# main.net
KiCad netlist of a schematic drawn in EAGLE
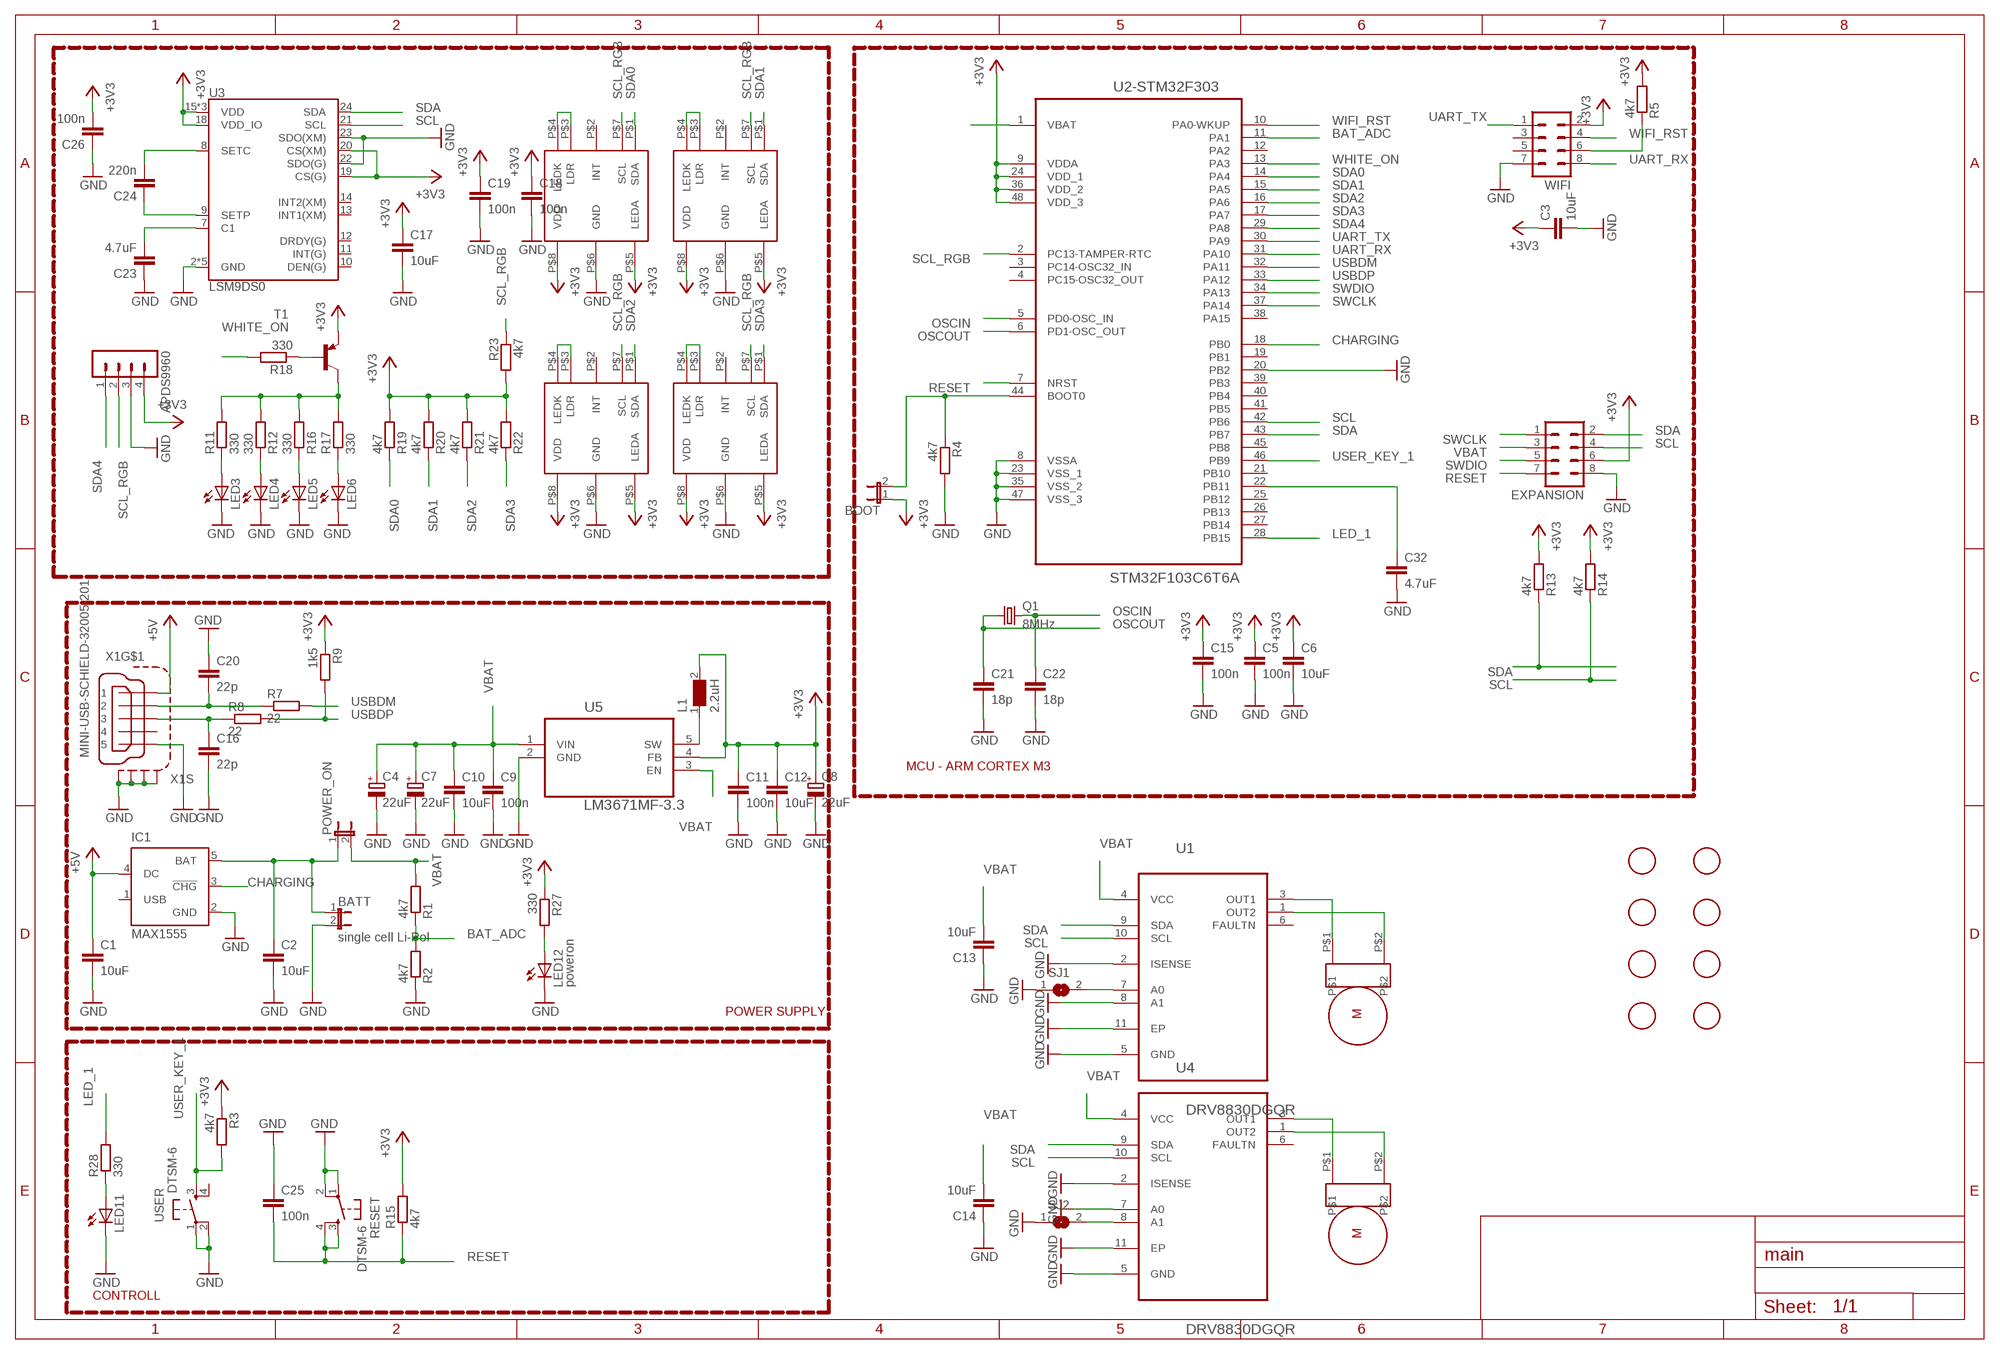
[diagram p0: schematic, sheet 1]

(export (version "E")
  (design (tool "Eeschema 10.0.6"))
  (components
    (comp (ref "APDS9960")
      (value "MA04-1")
      (footprint "eagle-import:MA04-1")
      (libsource (lib "eagle-import") (part "MA04-1"))
    )
    (comp (ref "BATT")
      (value "single cell Li-Pol")
      (footprint "eagle-import:JP1")
      (libsource (lib "eagle-import") (part "JP1E"))
    )
    (comp (ref "BOOT")
      (value "JP1E")
      (footprint "eagle-import:JP1")
      (libsource (lib "eagle-import") (part "JP1E"))
    )
    (comp (ref "C1")
      (value "10uF")
      (footprint "eagle-import:C0805")
      (libsource (lib "eagle-import") (part "C-EUC0805"))
    )
    (comp (ref "C2")
      (value "10uF")
      (footprint "eagle-import:C0805")
      (libsource (lib "eagle-import") (part "C-EUC0805"))
    )
    (comp (ref "C3")
      (value "10uF")
      (footprint "eagle-import:C0805")
      (libsource (lib "eagle-import") (part "C-EUC0805"))
    )
    (comp (ref "C4")
      (value "22uF")
      (footprint "eagle-import:153CLV-0505")
      (libsource (lib "eagle-import") (part "CPOL-EU153CLV-0505"))
    )
    (comp (ref "C5")
      (value "100n")
      (footprint "eagle-import:C0805")
      (libsource (lib "eagle-import") (part "C-EUC0805"))
    )
    (comp (ref "C6")
      (value "10uF")
      (footprint "eagle-import:C0805")
      (libsource (lib "eagle-import") (part "C-EUC0805"))
    )
    (comp (ref "C7")
      (value "22uF")
      (footprint "eagle-import:153CLV-0505")
      (libsource (lib "eagle-import") (part "CPOL-EU153CLV-0505"))
    )
    (comp (ref "C8")
      (value "22uF")
      (footprint "eagle-import:153CLV-0505")
      (libsource (lib "eagle-import") (part "CPOL-EU153CLV-0505"))
    )
    (comp (ref "C9")
      (value "100n")
      (footprint "eagle-import:C0805")
      (libsource (lib "eagle-import") (part "C-EUC0805"))
    )
    (comp (ref "C10")
      (value "10uF")
      (footprint "eagle-import:C0805")
      (libsource (lib "eagle-import") (part "C-EUC0805"))
    )
    (comp (ref "C11")
      (value "100n")
      (footprint "eagle-import:C0805")
      (libsource (lib "eagle-import") (part "C-EUC0805"))
    )
    (comp (ref "C12")
      (value "10uF")
      (footprint "eagle-import:C0805")
      (libsource (lib "eagle-import") (part "C-EUC0805"))
    )
    (comp (ref "C13")
      (value "10uF")
      (footprint "eagle-import:C0805")
      (libsource (lib "eagle-import") (part "C-EUC0805"))
    )
    (comp (ref "C14")
      (value "10uF")
      (footprint "eagle-import:C0805")
      (libsource (lib "eagle-import") (part "C-EUC0805"))
    )
    (comp (ref "C15")
      (value "100n")
      (footprint "eagle-import:C0805")
      (libsource (lib "eagle-import") (part "C-EUC0805"))
    )
    (comp (ref "C16")
      (value "22p")
      (footprint "eagle-import:C0805")
      (libsource (lib "eagle-import") (part "C-EUC0805"))
    )
    (comp (ref "C17")
      (value "10uF")
      (footprint "eagle-import:C0805")
      (libsource (lib "eagle-import") (part "C-EUC0805"))
    )
    (comp (ref "C18")
      (value "100n")
      (footprint "eagle-import:C0805")
      (libsource (lib "eagle-import") (part "C-EUC0805"))
    )
    (comp (ref "C19")
      (value "100n")
      (footprint "eagle-import:C0805")
      (libsource (lib "eagle-import") (part "C-EUC0805"))
    )
    (comp (ref "C20")
      (value "22p")
      (footprint "eagle-import:C0805")
      (libsource (lib "eagle-import") (part "C-EUC0805"))
    )
    (comp (ref "C21")
      (value "18p")
      (footprint "eagle-import:C0805")
      (libsource (lib "eagle-import") (part "C-EUC0805"))
    )
    (comp (ref "C22")
      (value "18p")
      (footprint "eagle-import:C0805")
      (libsource (lib "eagle-import") (part "C-EUC0805"))
    )
    (comp (ref "C23")
      (value "4.7uF")
      (footprint "eagle-import:C0805")
      (libsource (lib "eagle-import") (part "C-EUC0805"))
    )
    (comp (ref "C24")
      (value "220n")
      (footprint "eagle-import:C0805")
      (libsource (lib "eagle-import") (part "C-EUC0805"))
    )
    (comp (ref "C25")
      (value "100n")
      (footprint "eagle-import:C0805")
      (libsource (lib "eagle-import") (part "C-EUC0805"))
    )
    (comp (ref "C26")
      (value "100n")
      (footprint "eagle-import:C0805")
      (libsource (lib "eagle-import") (part "C-EUC0805"))
    )
    (comp (ref "C32")
      (value "4.7uF")
      (footprint "eagle-import:C0805")
      (libsource (lib "eagle-import") (part "C-EUC0805"))
    )
    (comp (ref "EXPANSION")
      (value "MA04-2")
      (footprint "eagle-import:MA04-2")
      (libsource (lib "eagle-import") (part "MA04-2"))
    )
    (comp (ref "IC1")
      (value "MAX1555")
      (footprint "eagle-import:SOT23-5L")
      (fields (field (name "MF") "MAXIM") (field (name "MPN") "MAX1555EZK+T"))
      (libsource (lib "eagle-import") (part "MAX1555"))
    )
    (comp (ref "L1")
      (value "2.2uH")
      (footprint "eagle-import:WE-LQ_M")
      (fields (field (name "MPN") "744032002 "))
      (libsource (lib "eagle-import") (part "WE-LQ_M-744032002"))
    )
    (comp (ref "LED3")
      (value "LEDCHIPLED_1206")
      (footprint "eagle-import:CHIPLED_1206")
      (libsource (lib "eagle-import") (part "LEDCHIPLED_1206"))
    )
    (comp (ref "LED4")
      (value "LEDCHIPLED_1206")
      (footprint "eagle-import:CHIPLED_1206")
      (libsource (lib "eagle-import") (part "LEDCHIPLED_1206"))
    )
    (comp (ref "LED5")
      (value "LEDCHIPLED_1206")
      (footprint "eagle-import:CHIPLED_1206")
      (libsource (lib "eagle-import") (part "LEDCHIPLED_1206"))
    )
    (comp (ref "LED6")
      (value "LEDCHIPLED_1206")
      (footprint "eagle-import:CHIPLED_1206")
      (libsource (lib "eagle-import") (part "LEDCHIPLED_1206"))
    )
    (comp (ref "LED11")
      (value "LEDCHIPLED_1206")
      (footprint "eagle-import:CHIPLED_1206")
      (libsource (lib "eagle-import") (part "LEDCHIPLED_1206"))
    )
    (comp (ref "LED12")
      (value "poweron")
      (footprint "eagle-import:CHIPLED_1206")
      (libsource (lib "eagle-import") (part "LEDCHIPLED_1206"))
    )
    (comp (ref "POWER_ON")
      (value "JP1E")
      (footprint "eagle-import:JP1")
      (libsource (lib "eagle-import") (part "JP1E"))
    )
    (comp (ref "Q1")
      (value "8MHz")
      (footprint "eagle-import:CTS406")
      (libsource (lib "eagle-import") (part "CRYSTALCTS406"))
    )
    (comp (ref "R1")
      (value "4k7")
      (footprint "eagle-import:M0805")
      (libsource (lib "eagle-import") (part "R-EU_M0805"))
    )
    (comp (ref "R2")
      (value "4k7")
      (footprint "eagle-import:M0805")
      (libsource (lib "eagle-import") (part "R-EU_M0805"))
    )
    (comp (ref "R3")
      (value "4k7")
      (footprint "eagle-import:M1206")
      (libsource (lib "eagle-import") (part "R-EU_M1206"))
    )
    (comp (ref "R4")
      (value "4k7")
      (footprint "eagle-import:M0805")
      (libsource (lib "eagle-import") (part "R-EU_M0805"))
    )
    (comp (ref "R5")
      (value "4k7")
      (footprint "eagle-import:M0805")
      (libsource (lib "eagle-import") (part "R-EU_M0805"))
    )
    (comp (ref "R7")
      (value "22")
      (footprint "eagle-import:M0805")
      (libsource (lib "eagle-import") (part "R-EU_M0805"))
    )
    (comp (ref "R8")
      (value "22")
      (footprint "eagle-import:M0805")
      (libsource (lib "eagle-import") (part "R-EU_M0805"))
    )
    (comp (ref "R9")
      (value "1k5")
      (footprint "eagle-import:M0805")
      (libsource (lib "eagle-import") (part "R-EU_M0805"))
    )
    (comp (ref "R11")
      (value "330")
      (footprint "eagle-import:M0805")
      (libsource (lib "eagle-import") (part "R-EU_M0805"))
    )
    (comp (ref "R12")
      (value "330")
      (footprint "eagle-import:M0805")
      (libsource (lib "eagle-import") (part "R-EU_M0805"))
    )
    (comp (ref "R13")
      (value "4k7")
      (footprint "eagle-import:M0805")
      (libsource (lib "eagle-import") (part "R-EU_M0805"))
    )
    (comp (ref "R14")
      (value "4k7")
      (footprint "eagle-import:M0805")
      (libsource (lib "eagle-import") (part "R-EU_M0805"))
    )
    (comp (ref "R15")
      (value "4k7")
      (footprint "eagle-import:M0805")
      (libsource (lib "eagle-import") (part "R-EU_M0805"))
    )
    (comp (ref "R16")
      (value "330")
      (footprint "eagle-import:M0805")
      (libsource (lib "eagle-import") (part "R-EU_M0805"))
    )
    (comp (ref "R17")
      (value "330")
      (footprint "eagle-import:M0805")
      (libsource (lib "eagle-import") (part "R-EU_M0805"))
    )
    (comp (ref "R18")
      (value "330")
      (footprint "eagle-import:M0805")
      (libsource (lib "eagle-import") (part "R-EU_M0805"))
    )
    (comp (ref "R19")
      (value "4k7")
      (footprint "eagle-import:M0805")
      (libsource (lib "eagle-import") (part "R-EU_M0805"))
    )
    (comp (ref "R20")
      (value "4k7")
      (footprint "eagle-import:M0805")
      (libsource (lib "eagle-import") (part "R-EU_M0805"))
    )
    (comp (ref "R21")
      (value "4k7")
      (footprint "eagle-import:M0805")
      (libsource (lib "eagle-import") (part "R-EU_M0805"))
    )
    (comp (ref "R22")
      (value "4k7")
      (footprint "eagle-import:M0805")
      (libsource (lib "eagle-import") (part "R-EU_M0805"))
    )
    (comp (ref "R23")
      (value "4k7")
      (footprint "eagle-import:M0805")
      (libsource (lib "eagle-import") (part "R-EU_M0805"))
    )
    (comp (ref "R27")
      (value "330")
      (footprint "eagle-import:M0805")
      (libsource (lib "eagle-import") (part "R-EU_M0805"))
    )
    (comp (ref "R28")
      (value "330")
      (footprint "eagle-import:M0805")
      (libsource (lib "eagle-import") (part "R-EU_M0805"))
    )
    (comp (ref "RESET")
      (value "DTSM-6")
      (footprint "eagle-import:DTSM-6")
      (libsource (lib "eagle-import") (part "DTSM-6"))
    )
    (comp (ref "SJ1") (value "SJ") (footprint "eagle-import:SJ") (libsource (lib "eagle-import") (part "SJ")))
    (comp (ref "SJ2") (value "SJ") (footprint "eagle-import:SJ") (libsource (lib "eagle-import") (part "SJ")))
    (comp (ref "T1")
      (value "BC857A-PNP-SOT23-BEC")
      (footprint "eagle-import:SOT23-BEC")
      (libsource (lib "eagle-import") (part "-PNP-SOT23-BECBC857A"))
    )
    (comp (ref "U$1")
      (value "APDS9950")
      (footprint "eagle-import:APDS9950")
      (libsource (lib "eagle-import") (part "APDS9950"))
    )
    (comp (ref "U$2")
      (value "APDS9950")
      (footprint "eagle-import:APDS9950")
      (libsource (lib "eagle-import") (part "APDS9950"))
    )
    (comp (ref "U$3")
      (value "APDS9950")
      (footprint "eagle-import:APDS9950")
      (libsource (lib "eagle-import") (part "APDS9950"))
    )
    (comp (ref "U$4")
      (value "APDS9950")
      (footprint "eagle-import:APDS9950")
      (libsource (lib "eagle-import") (part "APDS9950"))
    )
    (comp (ref "U$5")
      (value "MICRO_METAL_GEAR_MOTOR")
      (footprint "eagle-import:MICRO_METAL_GEAR_MOTOR")
      (libsource (lib "eagle-import") (part "MICRO_METAL_GEAR_MOTOR"))
    )
    (comp (ref "U$6")
      (value "MICRO_METAL_GEAR_MOTOR")
      (footprint "eagle-import:MICRO_METAL_GEAR_MOTOR")
      (libsource (lib "eagle-import") (part "MICRO_METAL_GEAR_MOTOR"))
    )
    (comp (ref "U$9")
      (value "FIDUCIAL")
      (footprint "eagle-import:FIDUCIAL_1MM")
      (libsource (lib "eagle-import") (part "FIDUCIAL"))
    )
    (comp (ref "U$10")
      (value "FIDUCIAL")
      (footprint "eagle-import:FIDUCIAL_1MM")
      (libsource (lib "eagle-import") (part "FIDUCIAL"))
    )
    (comp (ref "U$11")
      (value "FIDUCIAL")
      (footprint "eagle-import:FIDUCIAL_1MM")
      (libsource (lib "eagle-import") (part "FIDUCIAL"))
    )
    (comp (ref "U$12")
      (value "FIDUCIAL")
      (footprint "eagle-import:FIDUCIAL_1MM")
      (libsource (lib "eagle-import") (part "FIDUCIAL"))
    )
    (comp (ref "U$13")
      (value "FIDUCIAL")
      (footprint "eagle-import:FIDUCIAL_1MM")
      (libsource (lib "eagle-import") (part "FIDUCIAL"))
    )
    (comp (ref "U$14")
      (value "FIDUCIAL")
      (footprint "eagle-import:FIDUCIAL_1MM")
      (libsource (lib "eagle-import") (part "FIDUCIAL"))
    )
    (comp (ref "U$15")
      (value "FIDUCIAL")
      (footprint "eagle-import:FIDUCIAL_1MM")
      (libsource (lib "eagle-import") (part "FIDUCIAL"))
    )
    (comp (ref "U$16")
      (value "FIDUCIAL")
      (footprint "eagle-import:FIDUCIAL_1MM")
      (libsource (lib "eagle-import") (part "FIDUCIAL"))
    )
    (comp (ref "U1")
      (value "DRV8830DGQR")
      (footprint "eagle-import:SOP65P640X110-15N")
      (libsource (lib "eagle-import") (part "DRV8830DGQR"))
    )
    (comp (ref "U2-STM32F303")
      (value "STM32F103C6T6A")
      (footprint "eagle-import:QFP50P900X900X160-48N")
      (libsource (lib "eagle-import") (part "STM32F103C6T6A"))
    )
    (comp (ref "U3")
      (value "LSM9DS0")
      (footprint "eagle-import:LGA-24")
      (libsource (lib "eagle-import") (part "LSM9DS0"))
    )
    (comp (ref "U4")
      (value "DRV8830DGQR")
      (footprint "eagle-import:SOP65P640X110-15N")
      (libsource (lib "eagle-import") (part "DRV8830DGQR"))
    )
    (comp (ref "U5")
      (value "LM3671MF-3.3")
      (footprint "eagle-import:SOT95P284X122-5N")
      (libsource (lib "eagle-import") (part "LM3671MF-3.3"))
    )
    (comp (ref "USER")
      (value "DTSM-6")
      (footprint "eagle-import:DTSM-6")
      (libsource (lib "eagle-import") (part "DTSM-6"))
    )
    (comp (ref "WIFI")
      (value "MA04-2")
      (footprint "eagle-import:MA04-2")
      (libsource (lib "eagle-import") (part "MA04-2"))
    )
    (comp (ref "X1")
      (value "MINI-USB-SCHIELD-32005-201")
      (footprint "eagle-import:32005-201")
      (libsource (lib "eagle-import") (part "MINI-USB-SCHIELD-32005-201"))
    )
  )
  (nets
    (net (code "1") (name "+3V3") (class "Default")
      (node (ref "APDS9960") (pin "4") (pinfunction "4_4") (pintype "passive"))
      (node (ref "BOOT") (pin "1") (pinfunction "1_1") (pintype "passive"))
      (node (ref "C11") (pin "1") (pinfunction "1_1") (pintype "passive"))
      (node (ref "C12") (pin "1") (pinfunction "1_1") (pintype "passive"))
      (node (ref "C15") (pin "1") (pinfunction "1_1") (pintype "passive"))
      (node (ref "C17") (pin "1") (pinfunction "1_1") (pintype "passive"))
      (node (ref "C18") (pin "1") (pinfunction "1_1") (pintype "passive"))
      (node (ref "C19") (pin "1") (pinfunction "1_1") (pintype "passive"))
      (node (ref "C26") (pin "2") (pinfunction "2_2") (pintype "passive"))
      (node (ref "C3") (pin "1") (pinfunction "1_1") (pintype "passive"))
      (node (ref "C5") (pin "1") (pinfunction "1_1") (pintype "passive"))
      (node (ref "C6") (pin "1") (pinfunction "1_1") (pintype "passive"))
      (node (ref "C8") (pin "+") (pinfunction "+_+") (pintype "passive"))
      (node (ref "EXPANSION") (pin "6") (pinfunction "6_6") (pintype "passive"))
      (node (ref "L1") (pin "2") (pinfunction "2_2") (pintype "passive"))
      (node (ref "R13") (pin "2") (pinfunction "2_2") (pintype "passive"))
      (node (ref "R14") (pin "2") (pinfunction "2_2") (pintype "passive"))
      (node (ref "R15") (pin "2") (pinfunction "2_2") (pintype "passive"))
      (node (ref "R19") (pin "2") (pinfunction "2_2") (pintype "passive"))
      (node (ref "R20") (pin "2") (pinfunction "2_2") (pintype "passive"))
      (node (ref "R21") (pin "2") (pinfunction "2_2") (pintype "passive"))
      (node (ref "R22") (pin "2") (pinfunction "2_2") (pintype "passive"))
      (node (ref "R23") (pin "2") (pinfunction "2_2") (pintype "passive"))
      (node (ref "R27") (pin "1") (pinfunction "1_1") (pintype "passive"))
      (node (ref "R3") (pin "1") (pinfunction "1_1") (pintype "passive"))
      (node (ref "R5") (pin "2") (pinfunction "2_2") (pintype "passive"))
      (node (ref "R9") (pin "1") (pinfunction "1_1") (pintype "passive"))
      (node (ref "T1") (pin "E") (pinfunction "E_E") (pintype "passive"))
      (node (ref "U$1") (pin "P$5") (pinfunction "LEDA_P$5") (pintype "bidirectional"))
      (node (ref "U$1") (pin "P$8") (pinfunction "VDD_P$8") (pintype "bidirectional"))
      (node (ref "U$2") (pin "P$5") (pinfunction "LEDA_P$5") (pintype "bidirectional"))
      (node (ref "U$2") (pin "P$8") (pinfunction "VDD_P$8") (pintype "bidirectional"))
      (node (ref "U$3") (pin "P$5") (pinfunction "LEDA_P$5") (pintype "bidirectional"))
      (node (ref "U$3") (pin "P$8") (pinfunction "VDD_P$8") (pintype "bidirectional"))
      (node (ref "U$4") (pin "P$5") (pinfunction "LEDA_P$5") (pintype "bidirectional"))
      (node (ref "U$4") (pin "P$8") (pinfunction "VDD_P$8") (pintype "bidirectional"))
      (node (ref "U2-STM32F303") (pin "24") (pinfunction "VDD_1_24") (pintype "power_in"))
      (node (ref "U2-STM32F303") (pin "36") (pinfunction "VDD_2_36") (pintype "power_in"))
      (node (ref "U2-STM32F303") (pin "48") (pinfunction "VDD_3_48") (pintype "power_in"))
      (node (ref "U2-STM32F303") (pin "9") (pinfunction "VDDA_9") (pintype "power_in"))
      (node (ref "U3") (pin "15") (pinfunction "VDD_15") (pintype "bidirectional"))
      (node (ref "U3") (pin "16") (pinfunction "VDD_16") (pintype "bidirectional"))
      (node (ref "U3") (pin "17") (pinfunction "VDD_17") (pintype "bidirectional"))
      (node (ref "U3") (pin "18") (pinfunction "VDD_IO_18") (pintype "bidirectional"))
      (node (ref "U3") (pin "19") (pinfunction "CS(G)_19") (pintype "bidirectional"))
      (node (ref "U3") (pin "20") (pinfunction "CS(XM)_20") (pintype "bidirectional"))
      (node (ref "U5") (pin "4") (pinfunction "FB_4") (pintype "passive"))
      (node (ref "WIFI") (pin "2") (pinfunction "2_2") (pintype "passive"))
    )
    (net (code "2") (name "+5V") (class "Default")
      (node (ref "C1") (pin "1") (pinfunction "1_1") (pintype "passive"))
      (node (ref "IC1") (pin "4") (pinfunction "DC_4") (pintype "input"))
      (node (ref "X1") (pin "1") (pinfunction "1_1") (pintype "passive"))
    )
    (net (code "3") (name "/BAT_ADC") (class "Default")
      (node (ref "R1") (pin "1") (pinfunction "1_1") (pintype "passive"))
      (node (ref "R2") (pin "2") (pinfunction "2_2") (pintype "passive"))
      (node (ref "U2-STM32F303") (pin "11") (pinfunction "PA1_11") (pintype "bidirectional"))
    )
    (net (code "4") (name "/CHARGING") (class "Default")
      (node (ref "IC1") (pin "3") (pinfunction "~{CHG}_3") (pintype "output"))
      (node (ref "U2-STM32F303") (pin "18") (pinfunction "PB0_18") (pintype "bidirectional"))
    )
    (net (code "5") (name "/LED_1") (class "Default")
      (node (ref "R28") (pin "2") (pinfunction "2_2") (pintype "passive"))
      (node (ref "U2-STM32F303") (pin "28") (pinfunction "PB15_28") (pintype "bidirectional"))
    )
    (net (code "6") (name "/OSCIN") (class "Default")
      (node (ref "C22") (pin "1") (pinfunction "1_1") (pintype "passive"))
      (node (ref "Q1") (pin "3") (pinfunction "2_3") (pintype "passive"))
      (node (ref "U2-STM32F303") (pin "5") (pinfunction "PD0-OSC_IN_5") (pintype "bidirectional"))
    )
    (net (code "7") (name "/OSCOUT") (class "Default")
      (node (ref "C21") (pin "1") (pinfunction "1_1") (pintype "passive"))
      (node (ref "Q1") (pin "1") (pinfunction "1_1") (pintype "passive"))
      (node (ref "U2-STM32F303") (pin "6") (pinfunction "PD1-OSC_OUT_6") (pintype "bidirectional"))
    )
    (net (code "8") (name "/RESET") (class "Default")
      (node (ref "C25") (pin "2") (pinfunction "2_2") (pintype "passive"))
      (node (ref "EXPANSION") (pin "7") (pinfunction "7_7") (pintype "passive"))
      (node (ref "R15") (pin "1") (pinfunction "1_1") (pintype "passive"))
      (node (ref "RESET") (pin "3") (pinfunction "3_3") (pintype "passive"))
      (node (ref "RESET") (pin "4") (pinfunction "4_4") (pintype "passive"))
      (node (ref "U2-STM32F303") (pin "7") (pinfunction "NRST_7") (pintype "bidirectional"))
    )
    (net (code "9") (name "/SCL") (class "Default")
      (node (ref "EXPANSION") (pin "4") (pinfunction "4_4") (pintype "passive"))
      (node (ref "R14") (pin "1") (pinfunction "1_1") (pintype "passive"))
      (node (ref "U1") (pin "10") (pinfunction "SCL_10") (pintype "input"))
      (node (ref "U2-STM32F303") (pin "42") (pinfunction "PB6_42") (pintype "bidirectional"))
      (node (ref "U3") (pin "21") (pinfunction "SCL_21") (pintype "bidirectional"))
      (node (ref "U4") (pin "10") (pinfunction "SCL_10") (pintype "input"))
    )
    (net (code "10") (name "/SCL_RGB") (class "Default")
      (node (ref "APDS9960") (pin "2") (pinfunction "2_2") (pintype "passive"))
      (node (ref "R23") (pin "1") (pinfunction "1_1") (pintype "passive"))
      (node (ref "U$1") (pin "P$7") (pinfunction "SCL_P$7") (pintype "bidirectional"))
      (node (ref "U$2") (pin "P$7") (pinfunction "SCL_P$7") (pintype "bidirectional"))
      (node (ref "U$3") (pin "P$7") (pinfunction "SCL_P$7") (pintype "bidirectional"))
      (node (ref "U$4") (pin "P$7") (pinfunction "SCL_P$7") (pintype "bidirectional"))
      (node (ref "U2-STM32F303") (pin "2") (pinfunction "PC13-TAMPER-RTC_2") (pintype "bidirectional"))
    )
    (net (code "11") (name "/SDA") (class "Default")
      (node (ref "EXPANSION") (pin "2") (pinfunction "2_2") (pintype "passive"))
      (node (ref "R13") (pin "1") (pinfunction "1_1") (pintype "passive"))
      (node (ref "U1") (pin "9") (pinfunction "SDA_9") (pintype "bidirectional"))
      (node (ref "U2-STM32F303") (pin "43") (pinfunction "PB7_43") (pintype "bidirectional"))
      (node (ref "U3") (pin "24") (pinfunction "SDA_24") (pintype "bidirectional"))
      (node (ref "U4") (pin "9") (pinfunction "SDA_9") (pintype "bidirectional"))
    )
    (net (code "12") (name "/SDA0") (class "Default")
      (node (ref "R19") (pin "1") (pinfunction "1_1") (pintype "passive"))
      (node (ref "U$1") (pin "P$1") (pinfunction "SDA_P$1") (pintype "bidirectional"))
      (node (ref "U2-STM32F303") (pin "14") (pinfunction "PA4_14") (pintype "bidirectional"))
    )
    (net (code "13") (name "/SDA1") (class "Default")
      (node (ref "R20") (pin "1") (pinfunction "1_1") (pintype "passive"))
      (node (ref "U$2") (pin "P$1") (pinfunction "SDA_P$1") (pintype "bidirectional"))
      (node (ref "U2-STM32F303") (pin "15") (pinfunction "PA5_15") (pintype "bidirectional"))
    )
    (net (code "14") (name "/SDA2") (class "Default")
      (node (ref "R21") (pin "1") (pinfunction "1_1") (pintype "passive"))
      (node (ref "U$3") (pin "P$1") (pinfunction "SDA_P$1") (pintype "bidirectional"))
      (node (ref "U2-STM32F303") (pin "16") (pinfunction "PA6_16") (pintype "bidirectional"))
    )
    (net (code "15") (name "/SDA3") (class "Default")
      (node (ref "R22") (pin "1") (pinfunction "1_1") (pintype "passive"))
      (node (ref "U$4") (pin "P$1") (pinfunction "SDA_P$1") (pintype "bidirectional"))
      (node (ref "U2-STM32F303") (pin "17") (pinfunction "PA7_17") (pintype "bidirectional"))
    )
    (net (code "16") (name "/SDA4") (class "Default")
      (node (ref "APDS9960") (pin "1") (pinfunction "1_1") (pintype "passive"))
      (node (ref "U2-STM32F303") (pin "29") (pinfunction "PA8_29") (pintype "bidirectional"))
    )
    (net (code "17") (name "/SWCLK") (class "Default")
      (node (ref "EXPANSION") (pin "1") (pinfunction "1_1") (pintype "passive"))
      (node (ref "U2-STM32F303") (pin "37") (pinfunction "PA14_37") (pintype "bidirectional"))
    )
    (net (code "18") (name "/SWDIO") (class "Default")
      (node (ref "EXPANSION") (pin "5") (pinfunction "5_5") (pintype "passive"))
      (node (ref "U2-STM32F303") (pin "34") (pinfunction "PA13_34") (pintype "bidirectional"))
    )
    (net (code "19") (name "/UART_RX") (class "Default")
      (node (ref "U2-STM32F303") (pin "31") (pinfunction "PA10_31") (pintype "bidirectional"))
      (node (ref "WIFI") (pin "8") (pinfunction "8_8") (pintype "passive"))
    )
    (net (code "20") (name "/UART_TX") (class "Default")
      (node (ref "U2-STM32F303") (pin "30") (pinfunction "PA9_30") (pintype "bidirectional"))
      (node (ref "WIFI") (pin "1") (pinfunction "1_1") (pintype "passive"))
    )
    (net (code "21") (name "/USBDM") (class "Default")
      (node (ref "R7") (pin "2") (pinfunction "2_2") (pintype "passive"))
      (node (ref "U2-STM32F303") (pin "32") (pinfunction "PA11_32") (pintype "bidirectional"))
    )
    (net (code "22") (name "/USBDP") (class "Default")
      (node (ref "R8") (pin "2") (pinfunction "2_2") (pintype "passive"))
      (node (ref "R9") (pin "2") (pinfunction "2_2") (pintype "passive"))
      (node (ref "U2-STM32F303") (pin "33") (pinfunction "PA12_33") (pintype "bidirectional"))
    )
    (net (code "23") (name "/USER_KEY_1") (class "Default")
      (node (ref "R3") (pin "2") (pinfunction "2_2") (pintype "passive"))
      (node (ref "U2-STM32F303") (pin "46") (pinfunction "PB9_46") (pintype "bidirectional"))
      (node (ref "USER") (pin "3") (pinfunction "3_3") (pintype "passive"))
    )
    (net (code "24") (name "/VBAT") (class "Default")
      (node (ref "C10") (pin "1") (pinfunction "1_1") (pintype "passive"))
      (node (ref "C13") (pin "2") (pinfunction "2_2") (pintype "passive"))
      (node (ref "C14") (pin "2") (pinfunction "2_2") (pintype "passive"))
      (node (ref "C4") (pin "+") (pinfunction "+_+") (pintype "passive"))
      (node (ref "C7") (pin "+") (pinfunction "+_+") (pintype "passive"))
      (node (ref "C9") (pin "1") (pinfunction "1_1") (pintype "passive"))
      (node (ref "EXPANSION") (pin "3") (pinfunction "3_3") (pintype "passive"))
      (node (ref "POWER_ON") (pin "2") (pinfunction "2_2") (pintype "passive"))
      (node (ref "R1") (pin "2") (pinfunction "2_2") (pintype "passive"))
      (node (ref "U1") (pin "4") (pinfunction "VCC_4") (pintype "power_in"))
      (node (ref "U4") (pin "4") (pinfunction "VCC_4") (pintype "power_in"))
      (node (ref "U5") (pin "1") (pinfunction "VIN_1") (pintype "input"))
      (node (ref "U5") (pin "3") (pinfunction "EN_3") (pintype "passive"))
    )
    (net (code "25") (name "/WHITE_ON") (class "Default")
      (node (ref "R18") (pin "2") (pinfunction "2_2") (pintype "passive"))
      (node (ref "U2-STM32F303") (pin "13") (pinfunction "PA3_13") (pintype "bidirectional"))
    )
    (net (code "26") (name "/WIFI_RST") (class "Default")
      (node (ref "U2-STM32F303") (pin "10") (pinfunction "PA0-WKUP_10") (pintype "bidirectional"))
      (node (ref "WIFI") (pin "4") (pinfunction "4_4") (pintype "passive"))
    )
    (net (code "27") (name "GND") (class "Default")
      (node (ref "APDS9960") (pin "3") (pinfunction "3_3") (pintype "passive"))
      (node (ref "BATT") (pin "2") (pinfunction "2_2") (pintype "passive"))
      (node (ref "C1") (pin "2") (pinfunction "2_2") (pintype "passive"))
      (node (ref "C10") (pin "2") (pinfunction "2_2") (pintype "passive"))
      (node (ref "C11") (pin "2") (pinfunction "2_2") (pintype "passive"))
      (node (ref "C12") (pin "2") (pinfunction "2_2") (pintype "passive"))
      (node (ref "C13") (pin "1") (pinfunction "1_1") (pintype "passive"))
      (node (ref "C14") (pin "1") (pinfunction "1_1") (pintype "passive"))
      (node (ref "C15") (pin "2") (pinfunction "2_2") (pintype "passive"))
      (node (ref "C16") (pin "2") (pinfunction "2_2") (pintype "passive"))
      (node (ref "C17") (pin "2") (pinfunction "2_2") (pintype "passive"))
      (node (ref "C18") (pin "2") (pinfunction "2_2") (pintype "passive"))
      (node (ref "C19") (pin "2") (pinfunction "2_2") (pintype "passive"))
      (node (ref "C2") (pin "2") (pinfunction "2_2") (pintype "passive"))
      (node (ref "C20") (pin "1") (pinfunction "1_1") (pintype "passive"))
      (node (ref "C21") (pin "2") (pinfunction "2_2") (pintype "passive"))
      (node (ref "C22") (pin "2") (pinfunction "2_2") (pintype "passive"))
      (node (ref "C23") (pin "1") (pinfunction "1_1") (pintype "passive"))
      (node (ref "C25") (pin "1") (pinfunction "1_1") (pintype "passive"))
      (node (ref "C26") (pin "1") (pinfunction "1_1") (pintype "passive"))
      (node (ref "C3") (pin "2") (pinfunction "2_2") (pintype "passive"))
      (node (ref "C32") (pin "2") (pinfunction "2_2") (pintype "passive"))
      (node (ref "C4") (pin "-") (pinfunction "-_-") (pintype "passive"))
      (node (ref "C5") (pin "2") (pinfunction "2_2") (pintype "passive"))
      (node (ref "C6") (pin "2") (pinfunction "2_2") (pintype "passive"))
      (node (ref "C7") (pin "-") (pinfunction "-_-") (pintype "passive"))
      (node (ref "C8") (pin "-") (pinfunction "-_-") (pintype "passive"))
      (node (ref "C9") (pin "2") (pinfunction "2_2") (pintype "passive"))
      (node (ref "EXPANSION") (pin "8") (pinfunction "8_8") (pintype "passive"))
      (node (ref "IC1") (pin "2") (pinfunction "GND_2") (pintype "power_in"))
      (node (ref "LED11") (pin "C") (pinfunction "C_C") (pintype "passive"))
      (node (ref "LED12") (pin "C") (pinfunction "C_C") (pintype "passive"))
      (node (ref "LED3") (pin "C") (pinfunction "C_C") (pintype "passive"))
      (node (ref "LED4") (pin "C") (pinfunction "C_C") (pintype "passive"))
      (node (ref "LED5") (pin "C") (pinfunction "C_C") (pintype "passive"))
      (node (ref "LED6") (pin "C") (pinfunction "C_C") (pintype "passive"))
      (node (ref "R2") (pin "1") (pinfunction "1_1") (pintype "passive"))
      (node (ref "R4") (pin "2") (pinfunction "2_2") (pintype "passive"))
      (node (ref "RESET") (pin "1") (pinfunction "1_1") (pintype "passive"))
      (node (ref "RESET") (pin "2") (pinfunction "2_2") (pintype "passive"))
      (node (ref "SJ1") (pin "1") (pinfunction "1_1") (pintype "passive"))
      (node (ref "SJ2") (pin "1") (pinfunction "1_1") (pintype "passive"))
      (node (ref "U$1") (pin "P$6") (pinfunction "GND_P$6") (pintype "bidirectional"))
      (node (ref "U$2") (pin "P$6") (pinfunction "GND_P$6") (pintype "bidirectional"))
      (node (ref "U$3") (pin "P$6") (pinfunction "GND_P$6") (pintype "bidirectional"))
      (node (ref "U$4") (pin "P$6") (pinfunction "GND_P$6") (pintype "bidirectional"))
      (node (ref "U1") (pin "11") (pinfunction "EP_11") (pintype "passive"))
      (node (ref "U1") (pin "2") (pinfunction "ISENSE_2") (pintype "input"))
      (node (ref "U1") (pin "5") (pinfunction "GND_5") (pintype "passive"))
      (node (ref "U1") (pin "8") (pinfunction "A1_8") (pintype "input"))
      (node (ref "U2-STM32F303") (pin "20") (pinfunction "PB2_20") (pintype "bidirectional"))
      (node (ref "U2-STM32F303") (pin "23") (pinfunction "VSS_1_23") (pintype "passive"))
      (node (ref "U2-STM32F303") (pin "35") (pinfunction "VSS_2_35") (pintype "passive"))
      (node (ref "U2-STM32F303") (pin "47") (pinfunction "VSS_3_47") (pintype "passive"))
      (node (ref "U2-STM32F303") (pin "8") (pinfunction "VSSA_8") (pintype "passive"))
      (node (ref "U3") (pin "2") (pinfunction "GND_2") (pintype "bidirectional"))
      (node (ref "U3") (pin "22") (pinfunction "SDO(G)_22") (pintype "bidirectional"))
      (node (ref "U3") (pin "23") (pinfunction "SDO(XM)_23") (pintype "bidirectional"))
      (node (ref "U3") (pin "3") (pinfunction "GND_3") (pintype "bidirectional"))
      (node (ref "U3") (pin "4") (pinfunction "GND_4") (pintype "bidirectional"))
      (node (ref "U3") (pin "5") (pinfunction "GND_5") (pintype "bidirectional"))
      (node (ref "U3") (pin "6") (pinfunction "GND_6") (pintype "bidirectional"))
      (node (ref "U4") (pin "11") (pinfunction "EP_11") (pintype "passive"))
      (node (ref "U4") (pin "2") (pinfunction "ISENSE_2") (pintype "input"))
      (node (ref "U4") (pin "5") (pinfunction "GND_5") (pintype "passive"))
      (node (ref "U4") (pin "7") (pinfunction "A0_7") (pintype "input"))
      (node (ref "U5") (pin "2") (pinfunction "GND_2") (pintype "passive"))
      (node (ref "USER") (pin "1") (pinfunction "1_1") (pintype "passive"))
      (node (ref "USER") (pin "2") (pinfunction "2_2") (pintype "passive"))
      (node (ref "WIFI") (pin "7") (pinfunction "7_7") (pintype "passive"))
      (node (ref "X1") (pin "5") (pinfunction "5_5") (pintype "passive"))
      (node (ref "X1") (pin "M1") (pinfunction "S1_M1") (pintype "passive"))
      (node (ref "X1") (pin "M2") (pinfunction "S2_M2") (pintype "passive"))
      (node (ref "X1") (pin "M3") (pinfunction "S3_M3") (pintype "passive"))
      (node (ref "X1") (pin "M4") (pinfunction "S4_M4") (pintype "passive"))
    )
    (net (code "28") (name "Net-(C16-Pad1)") (class "Default")
      (node (ref "C16") (pin "1") (pinfunction "1_1") (pintype "passive"))
      (node (ref "R8") (pin "1") (pinfunction "1_1") (pintype "passive"))
      (node (ref "X1") (pin "3") (pinfunction "3_3") (pintype "passive"))
    )
    (net (code "29") (name "Net-(C20-Pad2)") (class "Default")
      (node (ref "C20") (pin "2") (pinfunction "2_2") (pintype "passive"))
      (node (ref "R7") (pin "1") (pinfunction "1_1") (pintype "passive"))
      (node (ref "X1") (pin "2") (pinfunction "2_2") (pintype "passive"))
    )
    (net (code "30") (name "Net-(IC1-BAT)") (class "Default")
      (node (ref "BATT") (pin "1") (pinfunction "1_1") (pintype "passive"))
      (node (ref "C2") (pin "1") (pinfunction "1_1") (pintype "passive"))
      (node (ref "IC1") (pin "5") (pinfunction "BAT_5") (pintype "passive"))
      (node (ref "POWER_ON") (pin "1") (pinfunction "1_1") (pintype "passive"))
    )
    (net (code "31") (name "Net-(LED3-PadA)") (class "Default")
      (node (ref "LED3") (pin "A") (pinfunction "A_A") (pintype "passive"))
      (node (ref "R11") (pin "1") (pinfunction "1_1") (pintype "passive"))
    )
    (net (code "32") (name "Net-(LED4-PadA)") (class "Default")
      (node (ref "LED4") (pin "A") (pinfunction "A_A") (pintype "passive"))
      (node (ref "R12") (pin "1") (pinfunction "1_1") (pintype "passive"))
    )
    (net (code "33") (name "Net-(LED5-PadA)") (class "Default")
      (node (ref "LED5") (pin "A") (pinfunction "A_A") (pintype "passive"))
      (node (ref "R16") (pin "1") (pinfunction "1_1") (pintype "passive"))
    )
    (net (code "34") (name "Net-(LED6-PadA)") (class "Default")
      (node (ref "LED6") (pin "A") (pinfunction "A_A") (pintype "passive"))
      (node (ref "R17") (pin "1") (pinfunction "1_1") (pintype "passive"))
    )
    (net (code "35") (name "Net-(LED11-PadA)") (class "Default")
      (node (ref "LED11") (pin "A") (pinfunction "A_A") (pintype "passive"))
      (node (ref "R28") (pin "1") (pinfunction "1_1") (pintype "passive"))
    )
    (net (code "36") (name "Net-(LED12-PadA)") (class "Default")
      (node (ref "LED12") (pin "A") (pinfunction "A_A") (pintype "passive"))
      (node (ref "R27") (pin "2") (pinfunction "2_2") (pintype "passive"))
    )
    (net (code "37") (name "Net-(R5-Pad1)") (class "Default")
      (node (ref "R5") (pin "1") (pinfunction "1_1") (pintype "passive"))
      (node (ref "WIFI") (pin "6") (pinfunction "6_6") (pintype "passive"))
    )
    (net (code "38") (name "Net-(R11-Pad2)") (class "Default")
      (node (ref "R11") (pin "2") (pinfunction "2_2") (pintype "passive"))
      (node (ref "R12") (pin "2") (pinfunction "2_2") (pintype "passive"))
      (node (ref "R16") (pin "2") (pinfunction "2_2") (pintype "passive"))
      (node (ref "R17") (pin "2") (pinfunction "2_2") (pintype "passive"))
      (node (ref "T1") (pin "C") (pinfunction "C_C") (pintype "passive"))
    )
    (net (code "39") (name "Net-(R18-Pad1)") (class "Default")
      (node (ref "R18") (pin "1") (pinfunction "1_1") (pintype "passive"))
      (node (ref "T1") (pin "B") (pinfunction "B_B") (pintype "passive"))
    )
    (net (code "40") (name "Net-(U$1-LDR)") (class "Default")
      (node (ref "U$1") (pin "P$3") (pinfunction "LDR_P$3") (pintype "bidirectional"))
      (node (ref "U$1") (pin "P$4") (pinfunction "LEDK_P$4") (pintype "bidirectional"))
    )
    (net (code "41") (name "Net-(U$2-LDR)") (class "Default")
      (node (ref "U$2") (pin "P$3") (pinfunction "LDR_P$3") (pintype "bidirectional"))
      (node (ref "U$2") (pin "P$4") (pinfunction "LEDK_P$4") (pintype "bidirectional"))
    )
    (net (code "42") (name "Net-(U$3-LDR)") (class "Default")
      (node (ref "U$3") (pin "P$3") (pinfunction "LDR_P$3") (pintype "bidirectional"))
      (node (ref "U$3") (pin "P$4") (pinfunction "LEDK_P$4") (pintype "bidirectional"))
    )
    (net (code "43") (name "Net-(U$4-LDR)") (class "Default")
      (node (ref "U$4") (pin "P$3") (pinfunction "LDR_P$3") (pintype "bidirectional"))
      (node (ref "U$4") (pin "P$4") (pinfunction "LEDK_P$4") (pintype "bidirectional"))
    )
    (net (code "44") (name "Net-(U1-A0)") (class "Default")
      (node (ref "SJ1") (pin "2") (pinfunction "2_2") (pintype "passive"))
      (node (ref "U1") (pin "7") (pinfunction "A0_7") (pintype "input"))
    )
    (net (code "45") (name "Net-(U1-OUT1)") (class "Default")
      (node (ref "U$5") (pin "P$1") (pinfunction "P$1_P$1") (pintype "bidirectional"))
      (node (ref "U1") (pin "3") (pinfunction "OUT1_3") (pintype "output"))
    )
    (net (code "46") (name "Net-(U1-OUT2)") (class "Default")
      (node (ref "U$5") (pin "P$2") (pinfunction "P$2_P$2") (pintype "bidirectional"))
      (node (ref "U1") (pin "1") (pinfunction "OUT2_1") (pintype "output"))
    )
    (net (code "47") (name "Net-(U2-STM32F303-BOOT0)") (class "Default")
      (node (ref "BOOT") (pin "2") (pinfunction "2_2") (pintype "passive"))
      (node (ref "R4") (pin "1") (pinfunction "1_1") (pintype "passive"))
      (node (ref "U2-STM32F303") (pin "44") (pinfunction "BOOT0_44") (pintype "input"))
    )
    (net (code "48") (name "Net-(U2-STM32F303-PB11)") (class "Default")
      (node (ref "C32") (pin "1") (pinfunction "1_1") (pintype "passive"))
      (node (ref "U2-STM32F303") (pin "22") (pinfunction "PB11_22") (pintype "bidirectional"))
    )
    (net (code "49") (name "Net-(U3-C1)") (class "Default")
      (node (ref "C23") (pin "2") (pinfunction "2_2") (pintype "passive"))
      (node (ref "U3") (pin "7") (pinfunction "C1_7") (pintype "bidirectional"))
    )
    (net (code "50") (name "Net-(U3-SETC)") (class "Default")
      (node (ref "C24") (pin "2") (pinfunction "2_2") (pintype "passive"))
      (node (ref "U3") (pin "8") (pinfunction "SETC_8") (pintype "bidirectional"))
    )
    (net (code "51") (name "Net-(U3-SETP)") (class "Default")
      (node (ref "C24") (pin "1") (pinfunction "1_1") (pintype "passive"))
      (node (ref "U3") (pin "9") (pinfunction "SETP_9") (pintype "bidirectional"))
    )
    (net (code "52") (name "Net-(U4-A1)") (class "Default")
      (node (ref "SJ2") (pin "2") (pinfunction "2_2") (pintype "passive"))
      (node (ref "U4") (pin "8") (pinfunction "A1_8") (pintype "input"))
    )
    (net (code "53") (name "Net-(U4-OUT1)") (class "Default")
      (node (ref "U$6") (pin "P$1") (pinfunction "P$1_P$1") (pintype "bidirectional"))
      (node (ref "U4") (pin "3") (pinfunction "OUT1_3") (pintype "output"))
    )
    (net (code "54") (name "Net-(U4-OUT2)") (class "Default")
      (node (ref "U$6") (pin "P$2") (pinfunction "P$2_P$2") (pintype "bidirectional"))
      (node (ref "U4") (pin "1") (pinfunction "OUT2_1") (pintype "output"))
    )
    (net (code "55") (name "Net-(U5-SW)") (class "Default")
      (node (ref "L1") (pin "1") (pinfunction "1_1") (pintype "passive"))
      (node (ref "U5") (pin "5") (pinfunction "SW_5") (pintype "output"))
    )
    (net (code "56") (name "unconnected-(IC1-USB-Pad1)") (class "Default")
      (node (ref "IC1") (pin "1") (pinfunction "USB_1") (pintype "input"))
    )
    (net (code "57") (name "unconnected-(U$1-INT-PadP$2)") (class "Default")
      (node (ref "U$1") (pin "P$2") (pinfunction "INT_P$2") (pintype "bidirectional"))
    )
    (net (code "58") (name "unconnected-(U$2-INT-PadP$2)") (class "Default")
      (node (ref "U$2") (pin "P$2") (pinfunction "INT_P$2") (pintype "bidirectional"))
    )
    (net (code "59") (name "unconnected-(U$3-INT-PadP$2)") (class "Default")
      (node (ref "U$3") (pin "P$2") (pinfunction "INT_P$2") (pintype "bidirectional"))
    )
    (net (code "60") (name "unconnected-(U$4-INT-PadP$2)") (class "Default")
      (node (ref "U$4") (pin "P$2") (pinfunction "INT_P$2") (pintype "bidirectional"))
    )
    (net (code "61") (name "unconnected-(U1-FAULTN-Pad6)") (class "Default")
      (node (ref "U1") (pin "6") (pinfunction "FAULTN_6") (pintype "output"))
    )
    (net (code "62") (name "unconnected-(U2-STM32F303-PA2-Pad12)") (class "Default")
      (node (ref "U2-STM32F303") (pin "12") (pinfunction "PA2_12") (pintype "bidirectional"))
    )
    (net (code "63") (name "unconnected-(U2-STM32F303-PA15-Pad38)") (class "Default")
      (node (ref "U2-STM32F303") (pin "38") (pinfunction "PA15_38") (pintype "bidirectional"))
    )
    (net (code "64") (name "unconnected-(U2-STM32F303-PB1-Pad19)") (class "Default")
      (node (ref "U2-STM32F303") (pin "19") (pinfunction "PB1_19") (pintype "bidirectional"))
    )
    (net (code "65") (name "unconnected-(U2-STM32F303-PB3-Pad39)") (class "Default")
      (node (ref "U2-STM32F303") (pin "39") (pinfunction "PB3_39") (pintype "bidirectional"))
    )
    (net (code "66") (name "unconnected-(U2-STM32F303-PB4-Pad40)") (class "Default")
      (node (ref "U2-STM32F303") (pin "40") (pinfunction "PB4_40") (pintype "bidirectional"))
    )
    (net (code "67") (name "unconnected-(U2-STM32F303-PB5-Pad41)") (class "Default")
      (node (ref "U2-STM32F303") (pin "41") (pinfunction "PB5_41") (pintype "bidirectional"))
    )
    (net (code "68") (name "unconnected-(U2-STM32F303-PB8-Pad45)") (class "Default")
      (node (ref "U2-STM32F303") (pin "45") (pinfunction "PB8_45") (pintype "bidirectional"))
    )
    (net (code "69") (name "unconnected-(U2-STM32F303-PB10-Pad21)") (class "Default")
      (node (ref "U2-STM32F303") (pin "21") (pinfunction "PB10_21") (pintype "bidirectional"))
    )
    (net (code "70") (name "unconnected-(U2-STM32F303-PB12-Pad25)") (class "Default")
      (node (ref "U2-STM32F303") (pin "25") (pinfunction "PB12_25") (pintype "bidirectional"))
    )
    (net (code "71") (name "unconnected-(U2-STM32F303-PB13-Pad26)") (class "Default")
      (node (ref "U2-STM32F303") (pin "26") (pinfunction "PB13_26") (pintype "bidirectional"))
    )
    (net (code "72") (name "unconnected-(U2-STM32F303-PB14-Pad27)") (class "Default")
      (node (ref "U2-STM32F303") (pin "27") (pinfunction "PB14_27") (pintype "bidirectional"))
    )
    (net (code "73") (name "unconnected-(U2-STM32F303-PC14-OSC32_IN-Pad3)") (class "Default")
      (node (ref "U2-STM32F303") (pin "3") (pinfunction "PC14-OSC32_IN_3") (pintype "bidirectional"))
    )
    (net (code "74") (name "unconnected-(U2-STM32F303-PC15-OSC32_OUT-Pad4)") (class "Default")
      (node (ref "U2-STM32F303") (pin "4") (pinfunction "PC15-OSC32_OUT_4") (pintype "bidirectional"))
    )
    (net (code "75") (name "unconnected-(U2-STM32F303-VBAT-Pad1)") (class "Default")
      (node (ref "U2-STM32F303") (pin "1") (pinfunction "VBAT_1") (pintype "power_in"))
    )
    (net (code "76") (name "unconnected-(U3-DEN(G)-Pad10)") (class "Default")
      (node (ref "U3") (pin "10") (pinfunction "DEN(G)_10") (pintype "bidirectional"))
    )
    (net (code "77") (name "unconnected-(U3-DRDY(G)-Pad12)") (class "Default")
      (node (ref "U3") (pin "12") (pinfunction "DRDY(G)_12") (pintype "bidirectional"))
    )
    (net (code "78") (name "unconnected-(U3-INT(G)-Pad11)") (class "Default")
      (node (ref "U3") (pin "11") (pinfunction "INT(G)_11") (pintype "bidirectional"))
    )
    (net (code "79") (name "unconnected-(U3-INT1(XM)-Pad13)") (class "Default")
      (node (ref "U3") (pin "13") (pinfunction "INT1(XM)_13") (pintype "bidirectional"))
    )
    (net (code "80") (name "unconnected-(U3-INT2(XM)-Pad14)") (class "Default")
      (node (ref "U3") (pin "14") (pinfunction "INT2(XM)_14") (pintype "bidirectional"))
    )
    (net (code "81") (name "unconnected-(U4-FAULTN-Pad6)") (class "Default")
      (node (ref "U4") (pin "6") (pinfunction "FAULTN_6") (pintype "output"))
    )
    (net (code "82") (name "unconnected-(USER-Pad4)") (class "Default")
      (node (ref "USER") (pin "4") (pinfunction "4_4") (pintype "passive"))
    )
    (net (code "83") (name "unconnected-(WIFI-Pad3)") (class "Default")
      (node (ref "WIFI") (pin "3") (pinfunction "3_3") (pintype "passive"))
    )
    (net (code "84") (name "unconnected-(WIFI-Pad5)") (class "Default")
      (node (ref "WIFI") (pin "5") (pinfunction "5_5") (pintype "passive"))
    )
    (net (code "85") (name "unconnected-(X1-Pad4)") (class "Default")
      (node (ref "X1") (pin "4") (pinfunction "4_4") (pintype "passive"))
    )
  )
)
